# ProtoCAT.net
KiCad netlist of a schematic drawn in EAGLE
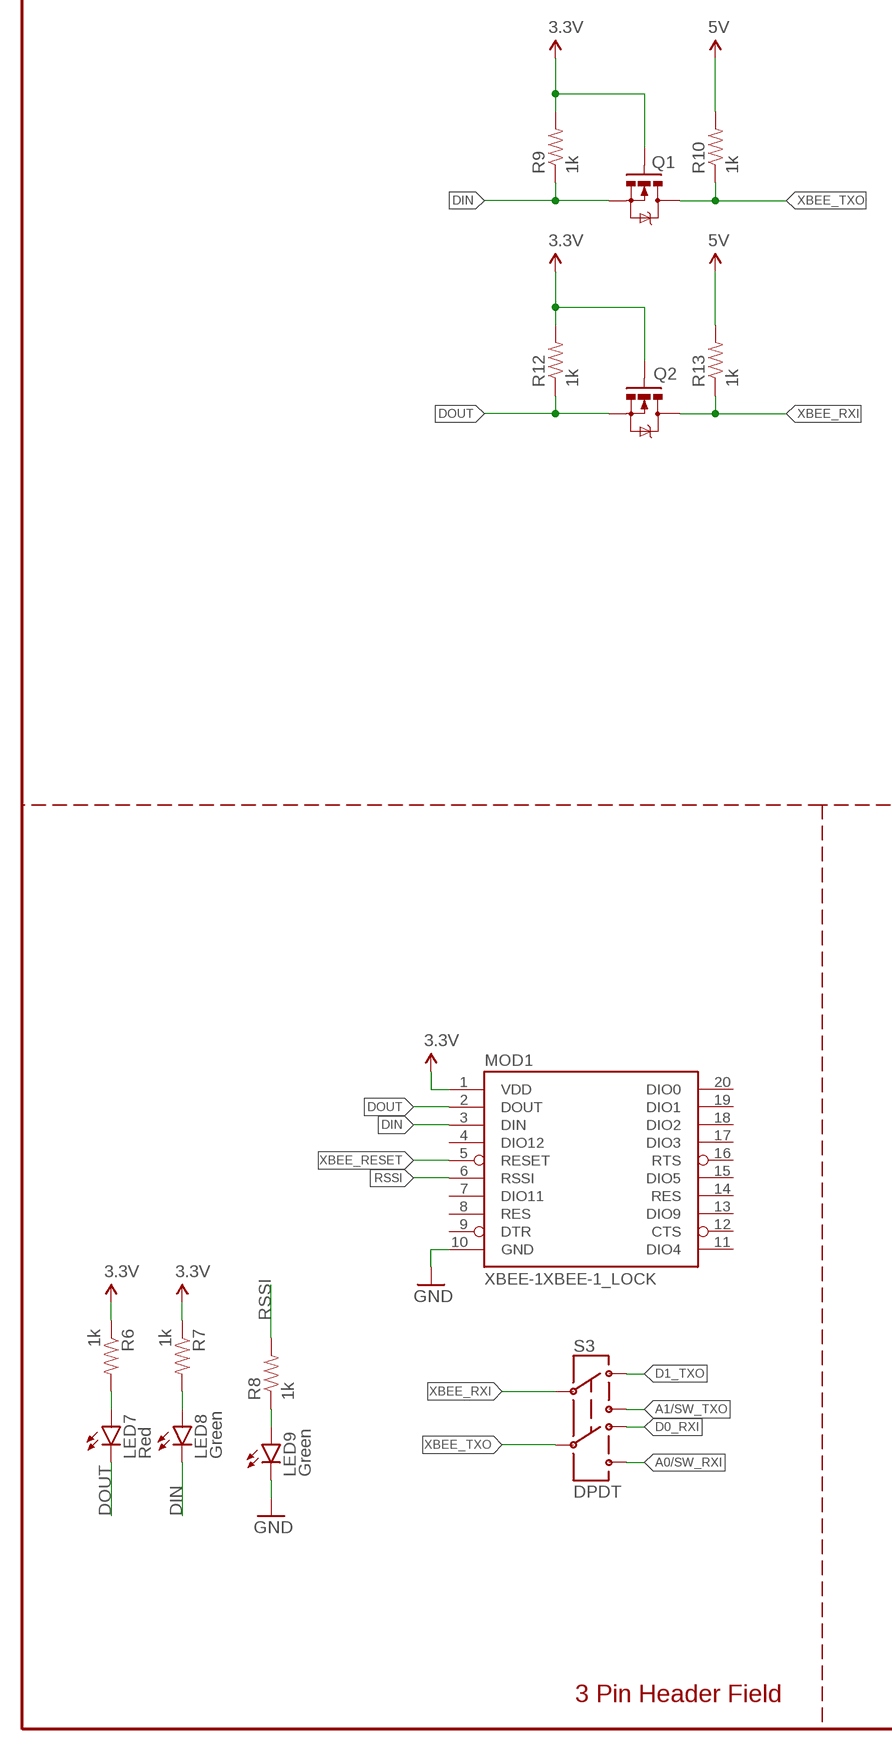
[diagram p0: schematic, sheet 1, part 1 of 2]
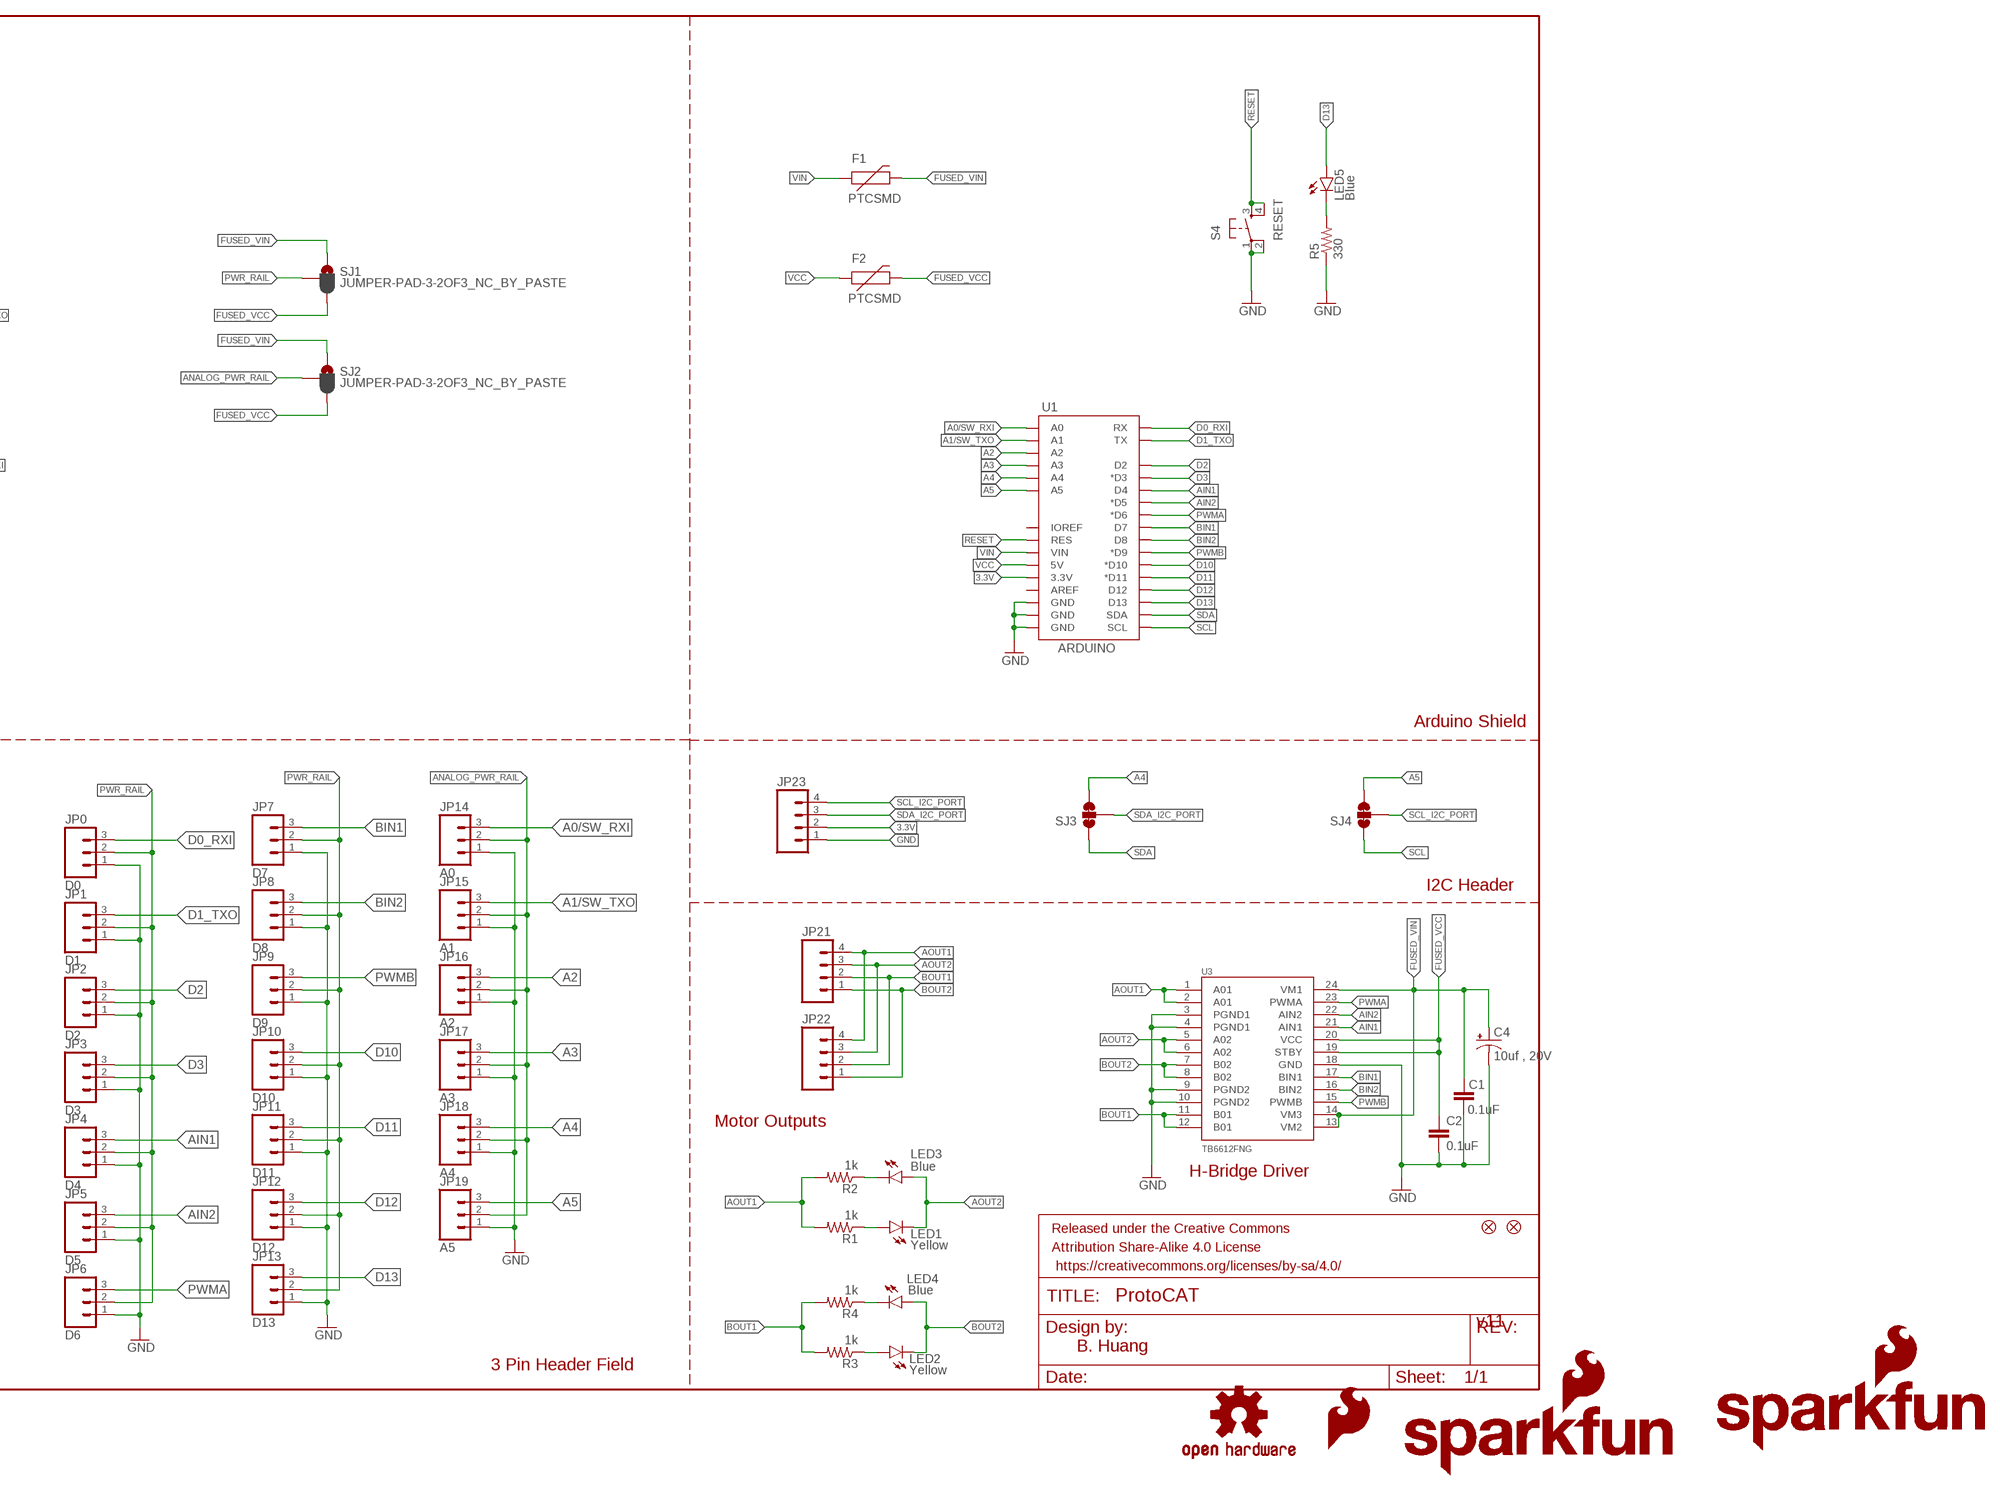
[diagram p1: schematic, sheet 1, part 2 of 2]

(export (version "E")
  (design (tool "Eeschema 10.0.6"))
  (components
    (comp (ref "C1")
      (value "0.1uF")
      (footprint "eagle-import:0603-CAP")
      (libsource (lib "eagle-import") (part "0.1UF-25V-5%(0603)"))
    )
    (comp (ref "C2")
      (value "0.1uF")
      (footprint "eagle-import:0603-CAP")
      (libsource (lib "eagle-import") (part "0.1UF-25V-5%(0603)"))
    )
    (comp (ref "C4")
      (value "10uf , 20V")
      (footprint "eagle-import:EIA3528")
      (libsource (lib "eagle-import") (part "10UF-20V-10%(TANT)"))
    )
    (comp (ref "F1")
      (value "PTCSMD")
      (footprint "eagle-import:PTC-1206")
      (libsource (lib "eagle-import") (part "PTCSMD"))
    )
    (comp (ref "F2")
      (value "PTCSMD")
      (footprint "eagle-import:PTC-1206")
      (libsource (lib "eagle-import") (part "PTCSMD"))
    )
    (comp (ref "FID1")
      (value "FIDUCIAL1X2")
      (footprint "eagle-import:FIDUCIAL-1X2")
      (libsource (lib "eagle-import") (part "FIDUCIAL1X2"))
    )
    (comp (ref "FID2")
      (value "FIDUCIAL1X2")
      (footprint "eagle-import:FIDUCIAL-1X2")
      (libsource (lib "eagle-import") (part "FIDUCIAL1X2"))
    )
    (comp (ref "FRAME1")
      (value "FRAME-LEDGER")
      (footprint "eagle-import:CREATIVE_COMMONS")
      (libsource (lib "eagle-import") (part "FRAME-LEDGER"))
    )
    (comp (ref "JP0")
      (value "D0")
      (footprint "eagle-import:1X03_LOCK")
      (libsource (lib "eagle-import") (part "M03LOCK"))
    )
    (comp (ref "JP1")
      (value "D1")
      (footprint "eagle-import:1X03_LOCK")
      (libsource (lib "eagle-import") (part "M03LOCK"))
    )
    (comp (ref "JP2")
      (value "D2")
      (footprint "eagle-import:1X03_LOCK")
      (libsource (lib "eagle-import") (part "M03LOCK"))
    )
    (comp (ref "JP3")
      (value "D3")
      (footprint "eagle-import:1X03_LOCK")
      (libsource (lib "eagle-import") (part "M03LOCK"))
    )
    (comp (ref "JP4")
      (value "D4")
      (footprint "eagle-import:1X03_LOCK")
      (libsource (lib "eagle-import") (part "M03LOCK"))
    )
    (comp (ref "JP5")
      (value "D5")
      (footprint "eagle-import:1X03_LOCK")
      (libsource (lib "eagle-import") (part "M03LOCK"))
    )
    (comp (ref "JP6")
      (value "D6")
      (footprint "eagle-import:1X03_LOCK")
      (libsource (lib "eagle-import") (part "M03LOCK"))
    )
    (comp (ref "JP7")
      (value "D7")
      (footprint "eagle-import:1X03_LOCK")
      (libsource (lib "eagle-import") (part "M03LOCK"))
    )
    (comp (ref "JP8")
      (value "D8")
      (footprint "eagle-import:1X03_LOCK")
      (libsource (lib "eagle-import") (part "M03LOCK"))
    )
    (comp (ref "JP9")
      (value "D9")
      (footprint "eagle-import:1X03_LOCK")
      (libsource (lib "eagle-import") (part "M03LOCK"))
    )
    (comp (ref "JP10")
      (value "D10")
      (footprint "eagle-import:1X03_LOCK")
      (libsource (lib "eagle-import") (part "M03LOCK"))
    )
    (comp (ref "JP11")
      (value "D11")
      (footprint "eagle-import:1X03_LOCK")
      (libsource (lib "eagle-import") (part "M03LOCK"))
    )
    (comp (ref "JP12")
      (value "D12")
      (footprint "eagle-import:1X03_LOCK")
      (libsource (lib "eagle-import") (part "M03LOCK"))
    )
    (comp (ref "JP13")
      (value "D13")
      (footprint "eagle-import:1X03_LOCK")
      (libsource (lib "eagle-import") (part "M03LOCK"))
    )
    (comp (ref "JP14")
      (value "A0")
      (footprint "eagle-import:1X03_LOCK")
      (libsource (lib "eagle-import") (part "M03LOCK"))
    )
    (comp (ref "JP15")
      (value "A1")
      (footprint "eagle-import:1X03_LOCK")
      (libsource (lib "eagle-import") (part "M03LOCK"))
    )
    (comp (ref "JP16")
      (value "A2")
      (footprint "eagle-import:1X03_LOCK")
      (libsource (lib "eagle-import") (part "M03LOCK"))
    )
    (comp (ref "JP17")
      (value "A3")
      (footprint "eagle-import:1X03_LOCK")
      (libsource (lib "eagle-import") (part "M03LOCK"))
    )
    (comp (ref "JP18")
      (value "A4")
      (footprint "eagle-import:1X03_LOCK")
      (libsource (lib "eagle-import") (part "M03LOCK"))
    )
    (comp (ref "JP19")
      (value "A5")
      (footprint "eagle-import:1X03_LOCK")
      (libsource (lib "eagle-import") (part "M03LOCK"))
    )
    (comp (ref "JP21")
      (value "M04PTH")
      (footprint "eagle-import:1X04")
      (libsource (lib "eagle-import") (part "M04PTH"))
    )
    (comp (ref "JP22")
      (value "M04SMD_STRAIGHT_COMBO")
      (footprint "eagle-import:1X04_SMD_STRAIGHT_COMBO")
      (libsource (lib "eagle-import") (part "M04SMD_STRAIGHT_COMBO"))
    )
    (comp (ref "JP23")
      (value "M04PTH")
      (footprint "eagle-import:1X04")
      (libsource (lib "eagle-import") (part "M04PTH"))
    )
    (comp (ref "LED1")
      (value "Yellow")
      (footprint "eagle-import:LED-0603")
      (libsource (lib "eagle-import") (part "LED0603"))
    )
    (comp (ref "LED2")
      (value "Yellow")
      (footprint "eagle-import:LED-0603")
      (libsource (lib "eagle-import") (part "LED0603"))
    )
    (comp (ref "LED3")
      (value "Blue")
      (footprint "eagle-import:LED-0603")
      (libsource (lib "eagle-import") (part "LED0603"))
    )
    (comp (ref "LED4")
      (value "Blue")
      (footprint "eagle-import:LED-0603")
      (libsource (lib "eagle-import") (part "LED0603"))
    )
    (comp (ref "LED5")
      (value "Blue")
      (footprint "eagle-import:LED-0603")
      (libsource (lib "eagle-import") (part "LED0603"))
    )
    (comp (ref "LED7")
      (value "Red")
      (footprint "eagle-import:LED-0603")
      (libsource (lib "eagle-import") (part "LED-RED0603"))
    )
    (comp (ref "LED8")
      (value "Green")
      (footprint "eagle-import:LED-0603")
      (libsource (lib "eagle-import") (part "LED-GREEN0603"))
    )
    (comp (ref "LED9")
      (value "Green")
      (footprint "eagle-import:LED-0603")
      (libsource (lib "eagle-import") (part "LED-GREEN0603"))
    )
    (comp (ref "LOGO1")
      (value "OSHW-LOGOM")
      (footprint "eagle-import:OSHW-LOGO-M")
      (libsource (lib "eagle-import") (part "OSHW-LOGOM"))
    )
    (comp (ref "LOGO2")
      (value "SFE_LOGO_NAME_FLAME.1_INCH")
      (footprint "eagle-import:SFE_LOGO_NAME_FLAME_.1")
      (libsource (lib "eagle-import") (part "SFE_LOGO_NAME_FLAME.1_INCH"))
    )
    (comp (ref "LOGO3")
      (value "SFE_LOGO_FLAME.2COP")
      (footprint "eagle-import:SFE_LOGO_FLAME_COPPER_.2")
      (libsource (lib "eagle-import") (part "SFE_LOGO_FLAME.2COP"))
    )
    (comp (ref "LOGO4")
      (value "SFE_LOGO_NAME_FLAME.1_INCH")
      (footprint "eagle-import:SFE_LOGO_NAME_FLAME_.1")
      (libsource (lib "eagle-import") (part "SFE_LOGO_NAME_FLAME.1_INCH"))
    )
    (comp (ref "MOD1")
      (value "XBEE-1XBEE-1_LOCK")
      (footprint "eagle-import:XBEE-1_LOCK")
      (libsource (lib "eagle-import") (part "XBEE-1XBEE-1_LOCK"))
    )
    (comp (ref "Q1")
      (value "MOSFET-NCHANNELSMD")
      (footprint "eagle-import:SOT23-3")
      (libsource (lib "eagle-import") (part "MOSFET-NCHANNELSMD"))
    )
    (comp (ref "Q2")
      (value "MOSFET-NCHANNELSMD")
      (footprint "eagle-import:SOT23-3")
      (libsource (lib "eagle-import") (part "MOSFET-NCHANNELSMD"))
    )
    (comp (ref "R1")
      (value "1k")
      (footprint "eagle-import:0603-RES")
      (libsource (lib "eagle-import") (part "1KOHM1/10W1%(0603)"))
    )
    (comp (ref "R2")
      (value "1k")
      (footprint "eagle-import:0603-RES")
      (libsource (lib "eagle-import") (part "1KOHM1/10W1%(0603)"))
    )
    (comp (ref "R3")
      (value "1k")
      (footprint "eagle-import:0603-RES")
      (libsource (lib "eagle-import") (part "1KOHM1/10W1%(0603)"))
    )
    (comp (ref "R4")
      (value "1k")
      (footprint "eagle-import:0603-RES")
      (libsource (lib "eagle-import") (part "1KOHM1/10W1%(0603)"))
    )
    (comp (ref "R5")
      (value "330")
      (footprint "eagle-import:0603-RES")
      (libsource (lib "eagle-import") (part "330OHM1/10W1%(0603)"))
    )
    (comp (ref "R6")
      (value "1k")
      (footprint "eagle-import:0603-RES")
      (libsource (lib "eagle-import") (part "1KOHM1/10W1%(0603)"))
    )
    (comp (ref "R7")
      (value "1k")
      (footprint "eagle-import:0603-RES")
      (libsource (lib "eagle-import") (part "1KOHM1/10W1%(0603)"))
    )
    (comp (ref "R8")
      (value "1k")
      (footprint "eagle-import:0603-RES")
      (libsource (lib "eagle-import") (part "1KOHM1/10W1%(0603)"))
    )
    (comp (ref "R9")
      (value "1k")
      (footprint "eagle-import:0603-RES")
      (libsource (lib "eagle-import") (part "1KOHM1/10W1%(0603)"))
    )
    (comp (ref "R10")
      (value "1k")
      (footprint "eagle-import:0603-RES")
      (libsource (lib "eagle-import") (part "1KOHM1/10W1%(0603)"))
    )
    (comp (ref "R12")
      (value "1k")
      (footprint "eagle-import:0603-RES")
      (libsource (lib "eagle-import") (part "1KOHM1/10W1%(0603)"))
    )
    (comp (ref "R13")
      (value "1k")
      (footprint "eagle-import:0603-RES")
      (libsource (lib "eagle-import") (part "1KOHM1/10W1%(0603)"))
    )
    (comp (ref "S3")
      (value "DPDT")
      (footprint "eagle-import:AYZ0202")
      (fields (field (name "PROD_ID") "SWCH-08179"))
      (libsource (lib "eagle-import") (part "SWITCH-DPDTAYZ0202"))
    )
    (comp (ref "S4")
      (value "RESET")
      (footprint "eagle-import:TACTILE-SWITCH-SMD")
      (libsource (lib "eagle-import") (part "TAC_SWITCHSMD"))
    )
    (comp (ref "SJ1")
      (value "JUMPER-PAD-3-2OF3_NC_BY_PASTE")
      (footprint "eagle-import:PAD-JUMPER-3-2OF3_NC_BY_PASTE_YES_SILK_FULL_BOX")
      (libsource (lib "eagle-import") (part "JUMPER-PAD-3-2OF3_NC_BY_PASTE"))
    )
    (comp (ref "SJ2")
      (value "JUMPER-PAD-3-2OF3_NC_BY_PASTE")
      (footprint "eagle-import:PAD-JUMPER-3-2OF3_NC_BY_PASTE_YES_SILK_FULL_BOX")
      (libsource (lib "eagle-import") (part "JUMPER-PAD-3-2OF3_NC_BY_PASTE"))
    )
    (comp (ref "SJ3")
      (value "JUMPER-PAD-3-NC_BY_TRACE")
      (footprint "eagle-import:PAD-JUMPER-3-3OF3_NC_BY_TRACE_YES_SILK_FULL_BOX")
      (libsource (lib "eagle-import") (part "JUMPER-PAD-3-NC_BY_TRACE"))
    )
    (comp (ref "SJ4")
      (value "JUMPER-PAD-3-NC_BY_TRACE")
      (footprint "eagle-import:PAD-JUMPER-3-3OF3_NC_BY_TRACE_YES_SILK_FULL_BOX")
      (libsource (lib "eagle-import") (part "JUMPER-PAD-3-NC_BY_TRACE"))
    )
    (comp (ref "U$1")
      (value "SFE_LUDUS")
      (footprint "eagle-import:SFE_LUDUS-M")
      (libsource (lib "eagle-import") (part "SFE_LUDUS"))
    )
    (comp (ref "U1")
      (value "ARDUINO")
      (footprint "eagle-import:UNO_R3_SHIELD_NOLABELS")
      (libsource (lib "eagle-import") (part "ARDUINO_R3_SHIELDNOLABELS"))
    )
    (comp (ref "U3")
      (value "TB6612FNG")
      (footprint "eagle-import:SSOP24")
      (libsource (lib "eagle-import") (part "TB6612FNG"))
    )
  )
  (nets
    (net (code "1") (name "3.3V") (class "Default")
      (node (ref "JP23") (pin "2") (pinfunction "2_2") (pintype "passive"))
      (node (ref "MOD1") (pin "1") (pinfunction "VDD_1") (pintype "power_in"))
      (node (ref "Q1") (pin "1") (pinfunction "G_1") (pintype "passive"))
      (node (ref "Q2") (pin "1") (pinfunction "G_1") (pintype "passive"))
      (node (ref "R12") (pin "2") (pinfunction "2_2") (pintype "passive"))
      (node (ref "R6") (pin "1") (pinfunction "1_1") (pintype "passive"))
      (node (ref "R7") (pin "1") (pinfunction "1_1") (pintype "passive"))
      (node (ref "R9") (pin "2") (pinfunction "2_2") (pintype "passive"))
      (node (ref "U1") (pin "3.3V") (pinfunction "3.3V_3.3V") (pintype "bidirectional"))
    )
    (net (code "2") (name "5V") (class "Default")
      (node (ref "R10") (pin "2") (pinfunction "2_2") (pintype "passive"))
      (node (ref "R13") (pin "2") (pinfunction "2_2") (pintype "passive"))
    )
    (net (code "3") (name "A0{slash}SW_RXI") (class "Default")
      (node (ref "JP14") (pin "3") (pinfunction "3_3") (pintype "passive"))
      (node (ref "S3") (pin "6") (pinfunction "6_6") (pintype "bidirectional"))
      (node (ref "U1") (pin "A0") (pinfunction "A0_A0") (pintype "bidirectional"))
    )
    (net (code "4") (name "A1{slash}SW_TXO") (class "Default")
      (node (ref "JP15") (pin "3") (pinfunction "3_3") (pintype "passive"))
      (node (ref "S3") (pin "3") (pinfunction "3_3") (pintype "bidirectional"))
      (node (ref "U1") (pin "A1") (pinfunction "A1_A1") (pintype "bidirectional"))
    )
    (net (code "5") (name "A2") (class "Default")
      (node (ref "JP16") (pin "3") (pinfunction "3_3") (pintype "passive"))
      (node (ref "U1") (pin "A2") (pinfunction "A2_A2") (pintype "bidirectional"))
    )
    (net (code "6") (name "A3") (class "Default")
      (node (ref "JP17") (pin "3") (pinfunction "3_3") (pintype "passive"))
      (node (ref "U1") (pin "A3") (pinfunction "A3_A3") (pintype "bidirectional"))
    )
    (net (code "7") (name "A4") (class "Default")
      (node (ref "JP18") (pin "3") (pinfunction "3_3") (pintype "passive"))
      (node (ref "SJ3") (pin "3") (pinfunction "3_3") (pintype "passive"))
      (node (ref "U1") (pin "A4") (pinfunction "A4_A4") (pintype "bidirectional"))
    )
    (net (code "8") (name "A5") (class "Default")
      (node (ref "JP19") (pin "3") (pinfunction "3_3") (pintype "passive"))
      (node (ref "SJ4") (pin "3") (pinfunction "3_3") (pintype "passive"))
      (node (ref "U1") (pin "A5") (pinfunction "A5_A5") (pintype "bidirectional"))
    )
    (net (code "9") (name "AIN1") (class "Default")
      (node (ref "JP4") (pin "3") (pinfunction "3_3") (pintype "passive"))
      (node (ref "U1") (pin "D4") (pinfunction "D4_D4") (pintype "bidirectional"))
      (node (ref "U3") (pin "21") (pinfunction "AIN1_21") (pintype "bidirectional"))
    )
    (net (code "10") (name "AIN2") (class "Default")
      (node (ref "JP5") (pin "3") (pinfunction "3_3") (pintype "passive"))
      (node (ref "U1") (pin "D5") (pinfunction "*D5_D5") (pintype "bidirectional"))
      (node (ref "U3") (pin "22") (pinfunction "AIN2_22") (pintype "bidirectional"))
    )
    (net (code "11") (name "ANALOG_PWR_RAIL") (class "Default")
      (node (ref "JP14") (pin "2") (pinfunction "2_2") (pintype "passive"))
      (node (ref "JP15") (pin "2") (pinfunction "2_2") (pintype "passive"))
      (node (ref "JP16") (pin "2") (pinfunction "2_2") (pintype "passive"))
      (node (ref "JP17") (pin "2") (pinfunction "2_2") (pintype "passive"))
      (node (ref "JP18") (pin "2") (pinfunction "2_2") (pintype "passive"))
      (node (ref "JP19") (pin "2") (pinfunction "2_2") (pintype "passive"))
      (node (ref "SJ2") (pin "2") (pinfunction "2_2") (pintype "passive"))
    )
    (net (code "12") (name "AOUT1") (class "Default")
      (node (ref "JP21") (pin "4") (pinfunction "4_4") (pintype "passive"))
      (node (ref "JP22") (pin "4") (pinfunction "4_4") (pintype "passive"))
      (node (ref "R1") (pin "2") (pinfunction "2_2") (pintype "passive"))
      (node (ref "R2") (pin "2") (pinfunction "2_2") (pintype "passive"))
      (node (ref "U3") (pin "1") (pinfunction "A01_1") (pintype "bidirectional"))
      (node (ref "U3") (pin "2") (pinfunction "A01_2") (pintype "bidirectional"))
    )
    (net (code "13") (name "AOUT2") (class "Default")
      (node (ref "JP21") (pin "3") (pinfunction "3_3") (pintype "passive"))
      (node (ref "JP22") (pin "3") (pinfunction "3_3") (pintype "passive"))
      (node (ref "LED1") (pin "C") (pinfunction "C_C") (pintype "passive"))
      (node (ref "LED3") (pin "A") (pinfunction "A_A") (pintype "passive"))
      (node (ref "U3") (pin "5") (pinfunction "A02_5") (pintype "bidirectional"))
      (node (ref "U3") (pin "6") (pinfunction "A02_6") (pintype "bidirectional"))
    )
    (net (code "14") (name "BIN1") (class "Default")
      (node (ref "JP7") (pin "3") (pinfunction "3_3") (pintype "passive"))
      (node (ref "U1") (pin "D7") (pinfunction "D7_D7") (pintype "bidirectional"))
      (node (ref "U3") (pin "17") (pinfunction "BIN1_17") (pintype "bidirectional"))
    )
    (net (code "15") (name "BIN2") (class "Default")
      (node (ref "JP8") (pin "3") (pinfunction "3_3") (pintype "passive"))
      (node (ref "U1") (pin "D8") (pinfunction "D8_D8") (pintype "bidirectional"))
      (node (ref "U3") (pin "16") (pinfunction "BIN2_16") (pintype "bidirectional"))
    )
    (net (code "16") (name "BOUT1") (class "Default")
      (node (ref "JP21") (pin "2") (pinfunction "2_2") (pintype "passive"))
      (node (ref "JP22") (pin "2") (pinfunction "2_2") (pintype "passive"))
      (node (ref "R3") (pin "2") (pinfunction "2_2") (pintype "passive"))
      (node (ref "R4") (pin "2") (pinfunction "2_2") (pintype "passive"))
      (node (ref "U3") (pin "11") (pinfunction "B01_11") (pintype "bidirectional"))
      (node (ref "U3") (pin "12") (pinfunction "B01_12") (pintype "bidirectional"))
    )
    (net (code "17") (name "BOUT2") (class "Default")
      (node (ref "JP21") (pin "1") (pinfunction "1_1") (pintype "passive"))
      (node (ref "JP22") (pin "1") (pinfunction "1_1") (pintype "passive"))
      (node (ref "LED2") (pin "C") (pinfunction "C_C") (pintype "passive"))
      (node (ref "LED4") (pin "A") (pinfunction "A_A") (pintype "passive"))
      (node (ref "U3") (pin "7") (pinfunction "B02_7") (pintype "bidirectional"))
      (node (ref "U3") (pin "8") (pinfunction "B02_8") (pintype "bidirectional"))
    )
    (net (code "18") (name "D0_RXI") (class "Default")
      (node (ref "JP0") (pin "3") (pinfunction "3_3") (pintype "passive"))
      (node (ref "S3") (pin "4") (pinfunction "4_4") (pintype "bidirectional"))
      (node (ref "U1") (pin "RX") (pinfunction "RX_RX") (pintype "bidirectional"))
    )
    (net (code "19") (name "D1_TXO") (class "Default")
      (node (ref "JP1") (pin "3") (pinfunction "3_3") (pintype "passive"))
      (node (ref "S3") (pin "1") (pinfunction "1_1") (pintype "bidirectional"))
      (node (ref "U1") (pin "TX") (pinfunction "TX_TX") (pintype "bidirectional"))
    )
    (net (code "20") (name "D2") (class "Default")
      (node (ref "JP2") (pin "3") (pinfunction "3_3") (pintype "passive"))
      (node (ref "U1") (pin "D2") (pinfunction "D2_D2") (pintype "bidirectional"))
    )
    (net (code "21") (name "D3") (class "Default")
      (node (ref "JP3") (pin "3") (pinfunction "3_3") (pintype "passive"))
      (node (ref "U1") (pin "D3") (pinfunction "*D3_D3") (pintype "bidirectional"))
    )
    (net (code "22") (name "D10") (class "Default")
      (node (ref "JP10") (pin "3") (pinfunction "3_3") (pintype "passive"))
      (node (ref "U1") (pin "D10") (pinfunction "*D10_D10") (pintype "bidirectional"))
    )
    (net (code "23") (name "D11") (class "Default")
      (node (ref "JP11") (pin "3") (pinfunction "3_3") (pintype "passive"))
      (node (ref "U1") (pin "D11") (pinfunction "*D11_D11") (pintype "bidirectional"))
    )
    (net (code "24") (name "D12") (class "Default")
      (node (ref "JP12") (pin "3") (pinfunction "3_3") (pintype "passive"))
      (node (ref "U1") (pin "D12") (pinfunction "D12_D12") (pintype "bidirectional"))
    )
    (net (code "25") (name "D13") (class "Default")
      (node (ref "JP13") (pin "3") (pinfunction "3_3") (pintype "passive"))
      (node (ref "LED5") (pin "A") (pinfunction "A_A") (pintype "passive"))
      (node (ref "U1") (pin "D13") (pinfunction "D13_D13") (pintype "bidirectional"))
    )
    (net (code "26") (name "DIN") (class "Default")
      (node (ref "LED8") (pin "C") (pinfunction "C_C") (pintype "passive"))
      (node (ref "MOD1") (pin "3") (pinfunction "DIN_3") (pintype "input"))
      (node (ref "Q1") (pin "2") (pinfunction "S_2") (pintype "passive"))
      (node (ref "R9") (pin "1") (pinfunction "1_1") (pintype "passive"))
    )
    (net (code "27") (name "DOUT") (class "Default")
      (node (ref "LED7") (pin "C") (pinfunction "C_C") (pintype "passive"))
      (node (ref "MOD1") (pin "2") (pinfunction "DOUT_2") (pintype "output"))
      (node (ref "Q2") (pin "2") (pinfunction "S_2") (pintype "passive"))
      (node (ref "R12") (pin "1") (pinfunction "1_1") (pintype "passive"))
    )
    (net (code "28") (name "FUSED_VCC") (class "Default")
      (node (ref "C2") (pin "1") (pinfunction "1_1") (pintype "passive"))
      (node (ref "F2") (pin "2") (pinfunction "2_2") (pintype "bidirectional"))
      (node (ref "SJ1") (pin "3") (pinfunction "3_3") (pintype "passive"))
      (node (ref "SJ2") (pin "3") (pinfunction "3_3") (pintype "passive"))
      (node (ref "U3") (pin "19") (pinfunction "STBY_19") (pintype "bidirectional"))
      (node (ref "U3") (pin "20") (pinfunction "VCC_20") (pintype "bidirectional"))
    )
    (net (code "29") (name "FUSED_VIN") (class "Default")
      (node (ref "C1") (pin "1") (pinfunction "1_1") (pintype "passive"))
      (node (ref "C4") (pin "A") (pinfunction "+_A") (pintype "passive"))
      (node (ref "F1") (pin "2") (pinfunction "2_2") (pintype "bidirectional"))
      (node (ref "SJ1") (pin "1") (pinfunction "1_1") (pintype "passive"))
      (node (ref "SJ2") (pin "1") (pinfunction "1_1") (pintype "passive"))
      (node (ref "U3") (pin "13") (pinfunction "VM2_13") (pintype "bidirectional"))
      (node (ref "U3") (pin "14") (pinfunction "VM3_14") (pintype "bidirectional"))
      (node (ref "U3") (pin "24") (pinfunction "VM1_24") (pintype "bidirectional"))
    )
    (net (code "30") (name "GND") (class "Default")
      (node (ref "C1") (pin "2") (pinfunction "2_2") (pintype "passive"))
      (node (ref "C2") (pin "2") (pinfunction "2_2") (pintype "passive"))
      (node (ref "C4") (pin "C") (pinfunction "-_C") (pintype "passive"))
      (node (ref "JP0") (pin "1") (pinfunction "1_1") (pintype "passive"))
      (node (ref "JP1") (pin "1") (pinfunction "1_1") (pintype "passive"))
      (node (ref "JP10") (pin "1") (pinfunction "1_1") (pintype "passive"))
      (node (ref "JP11") (pin "1") (pinfunction "1_1") (pintype "passive"))
      (node (ref "JP12") (pin "1") (pinfunction "1_1") (pintype "passive"))
      (node (ref "JP13") (pin "1") (pinfunction "1_1") (pintype "passive"))
      (node (ref "JP14") (pin "1") (pinfunction "1_1") (pintype "passive"))
      (node (ref "JP15") (pin "1") (pinfunction "1_1") (pintype "passive"))
      (node (ref "JP16") (pin "1") (pinfunction "1_1") (pintype "passive"))
      (node (ref "JP17") (pin "1") (pinfunction "1_1") (pintype "passive"))
      (node (ref "JP18") (pin "1") (pinfunction "1_1") (pintype "passive"))
      (node (ref "JP19") (pin "1") (pinfunction "1_1") (pintype "passive"))
      (node (ref "JP2") (pin "1") (pinfunction "1_1") (pintype "passive"))
      (node (ref "JP23") (pin "1") (pinfunction "1_1") (pintype "passive"))
      (node (ref "JP3") (pin "1") (pinfunction "1_1") (pintype "passive"))
      (node (ref "JP4") (pin "1") (pinfunction "1_1") (pintype "passive"))
      (node (ref "JP5") (pin "1") (pinfunction "1_1") (pintype "passive"))
      (node (ref "JP6") (pin "1") (pinfunction "1_1") (pintype "passive"))
      (node (ref "JP7") (pin "1") (pinfunction "1_1") (pintype "passive"))
      (node (ref "JP8") (pin "1") (pinfunction "1_1") (pintype "passive"))
      (node (ref "JP9") (pin "1") (pinfunction "1_1") (pintype "passive"))
      (node (ref "LED9") (pin "C") (pinfunction "C_C") (pintype "passive"))
      (node (ref "MOD1") (pin "10") (pinfunction "GND_10") (pintype "power_in"))
      (node (ref "R5") (pin "1") (pinfunction "1_1") (pintype "passive"))
      (node (ref "S4") (pin "1") (pinfunction "1_1") (pintype "passive"))
      (node (ref "S4") (pin "2") (pinfunction "2_2") (pintype "passive"))
      (node (ref "U1") (pin "GND@0") (pinfunction "GND_GND@0") (pintype "bidirectional"))
      (node (ref "U1") (pin "GND@1") (pinfunction "GND_GND@1") (pintype "bidirectional"))
      (node (ref "U1") (pin "GND@2") (pinfunction "GND_GND@2") (pintype "bidirectional"))
      (node (ref "U3") (pin "10") (pinfunction "PGND2_10") (pintype "bidirectional"))
      (node (ref "U3") (pin "18") (pinfunction "GND_18") (pintype "bidirectional"))
      (node (ref "U3") (pin "3") (pinfunction "PGND1_3") (pintype "bidirectional"))
      (node (ref "U3") (pin "4") (pinfunction "PGND1_4") (pintype "bidirectional"))
      (node (ref "U3") (pin "9") (pinfunction "PGND2_9") (pintype "bidirectional"))
    )
    (net (code "31") (name "Net-(LED1-PadA)") (class "Default")
      (node (ref "LED1") (pin "A") (pinfunction "A_A") (pintype "passive"))
      (node (ref "R1") (pin "1") (pinfunction "1_1") (pintype "passive"))
    )
    (net (code "32") (name "Net-(LED2-PadA)") (class "Default")
      (node (ref "LED2") (pin "A") (pinfunction "A_A") (pintype "passive"))
      (node (ref "R3") (pin "1") (pinfunction "1_1") (pintype "passive"))
    )
    (net (code "33") (name "Net-(LED3-PadC)") (class "Default")
      (node (ref "LED3") (pin "C") (pinfunction "C_C") (pintype "passive"))
      (node (ref "R2") (pin "1") (pinfunction "1_1") (pintype "passive"))
    )
    (net (code "34") (name "Net-(LED4-PadC)") (class "Default")
      (node (ref "LED4") (pin "C") (pinfunction "C_C") (pintype "passive"))
      (node (ref "R4") (pin "1") (pinfunction "1_1") (pintype "passive"))
    )
    (net (code "35") (name "Net-(LED5-PadC)") (class "Default")
      (node (ref "LED5") (pin "C") (pinfunction "C_C") (pintype "passive"))
      (node (ref "R5") (pin "2") (pinfunction "2_2") (pintype "passive"))
    )
    (net (code "36") (name "Net-(LED7-PadA)") (class "Default")
      (node (ref "LED7") (pin "A") (pinfunction "A_A") (pintype "passive"))
      (node (ref "R6") (pin "2") (pinfunction "2_2") (pintype "passive"))
    )
    (net (code "37") (name "Net-(LED8-PadA)") (class "Default")
      (node (ref "LED8") (pin "A") (pinfunction "A_A") (pintype "passive"))
      (node (ref "R7") (pin "2") (pinfunction "2_2") (pintype "passive"))
    )
    (net (code "38") (name "Net-(LED9-PadA)") (class "Default")
      (node (ref "LED9") (pin "A") (pinfunction "A_A") (pintype "passive"))
      (node (ref "R8") (pin "1") (pinfunction "1_1") (pintype "passive"))
    )
    (net (code "39") (name "PWMA") (class "Default")
      (node (ref "JP6") (pin "3") (pinfunction "3_3") (pintype "passive"))
      (node (ref "U1") (pin "D6") (pinfunction "*D6_D6") (pintype "bidirectional"))
      (node (ref "U3") (pin "23") (pinfunction "PWMA_23") (pintype "bidirectional"))
    )
    (net (code "40") (name "PWMB") (class "Default")
      (node (ref "JP9") (pin "3") (pinfunction "3_3") (pintype "passive"))
      (node (ref "U1") (pin "D9") (pinfunction "*D9_D9") (pintype "bidirectional"))
      (node (ref "U3") (pin "15") (pinfunction "PWMB_15") (pintype "bidirectional"))
    )
    (net (code "41") (name "PWR_RAIL") (class "Default")
      (node (ref "JP0") (pin "2") (pinfunction "2_2") (pintype "passive"))
      (node (ref "JP1") (pin "2") (pinfunction "2_2") (pintype "passive"))
      (node (ref "JP10") (pin "2") (pinfunction "2_2") (pintype "passive"))
      (node (ref "JP11") (pin "2") (pinfunction "2_2") (pintype "passive"))
      (node (ref "JP12") (pin "2") (pinfunction "2_2") (pintype "passive"))
      (node (ref "JP13") (pin "2") (pinfunction "2_2") (pintype "passive"))
      (node (ref "JP2") (pin "2") (pinfunction "2_2") (pintype "passive"))
      (node (ref "JP3") (pin "2") (pinfunction "2_2") (pintype "passive"))
      (node (ref "JP4") (pin "2") (pinfunction "2_2") (pintype "passive"))
      (node (ref "JP5") (pin "2") (pinfunction "2_2") (pintype "passive"))
      (node (ref "JP6") (pin "2") (pinfunction "2_2") (pintype "passive"))
      (node (ref "JP7") (pin "2") (pinfunction "2_2") (pintype "passive"))
      (node (ref "JP8") (pin "2") (pinfunction "2_2") (pintype "passive"))
      (node (ref "JP9") (pin "2") (pinfunction "2_2") (pintype "passive"))
      (node (ref "SJ1") (pin "2") (pinfunction "2_2") (pintype "passive"))
    )
    (net (code "42") (name "RESET") (class "Default")
      (node (ref "S4") (pin "3") (pinfunction "3_3") (pintype "passive"))
      (node (ref "S4") (pin "4") (pinfunction "4_4") (pintype "passive"))
      (node (ref "U1") (pin "RES") (pinfunction "RES_RES") (pintype "bidirectional"))
    )
    (net (code "43") (name "RSSI") (class "Default")
      (node (ref "MOD1") (pin "6") (pinfunction "RSSI_6") (pintype "bidirectional"))
      (node (ref "R8") (pin "2") (pinfunction "2_2") (pintype "passive"))
    )
    (net (code "44") (name "SCL") (class "Default")
      (node (ref "SJ4") (pin "1") (pinfunction "1_1") (pintype "passive"))
      (node (ref "U1") (pin "SCL") (pinfunction "SCL_SCL") (pintype "bidirectional"))
    )
    (net (code "45") (name "SCL_I2C_PORT") (class "Default")
      (node (ref "JP23") (pin "4") (pinfunction "4_4") (pintype "passive"))
      (node (ref "SJ4") (pin "2") (pinfunction "2_2") (pintype "passive"))
    )
    (net (code "46") (name "SDA") (class "Default")
      (node (ref "SJ3") (pin "1") (pinfunction "1_1") (pintype "passive"))
      (node (ref "U1") (pin "SDA") (pinfunction "SDA_SDA") (pintype "bidirectional"))
    )
    (net (code "47") (name "SDA_I2C_PORT") (class "Default")
      (node (ref "JP23") (pin "3") (pinfunction "3_3") (pintype "passive"))
      (node (ref "SJ3") (pin "2") (pinfunction "2_2") (pintype "passive"))
    )
    (net (code "48") (name "VCC") (class "Default")
      (node (ref "F2") (pin "1") (pinfunction "1_1") (pintype "bidirectional"))
      (node (ref "U1") (pin "5V") (pinfunction "5V_5V") (pintype "bidirectional"))
    )
    (net (code "49") (name "VIN") (class "Default")
      (node (ref "F1") (pin "1") (pinfunction "1_1") (pintype "bidirectional"))
      (node (ref "U1") (pin "VIN") (pinfunction "VIN_VIN") (pintype "bidirectional"))
    )
    (net (code "50") (name "XBEE_RESET") (class "Default")
      (node (ref "MOD1") (pin "5") (pinfunction "RESET_5") (pintype "input"))
    )
    (net (code "51") (name "XBEE_RXI") (class "Default")
      (node (ref "Q2") (pin "3") (pinfunction "D_3") (pintype "passive"))
      (node (ref "R13") (pin "1") (pinfunction "1_1") (pintype "passive"))
      (node (ref "S3") (pin "2") (pinfunction "2_2") (pintype "bidirectional"))
    )
    (net (code "52") (name "XBEE_TXO") (class "Default")
      (node (ref "Q1") (pin "3") (pinfunction "D_3") (pintype "passive"))
      (node (ref "R10") (pin "1") (pinfunction "1_1") (pintype "passive"))
      (node (ref "S3") (pin "5") (pinfunction "5_5") (pintype "bidirectional"))
    )
    (net (code "53") (name "unconnected-(MOD1-CTS-Pad12)") (class "Default")
      (node (ref "MOD1") (pin "12") (pinfunction "CTS_12") (pintype "output"))
    )
    (net (code "54") (name "unconnected-(MOD1-DIO0-Pad20)") (class "Default")
      (node (ref "MOD1") (pin "20") (pinfunction "DIO0_20") (pintype "bidirectional"))
    )
    (net (code "55") (name "unconnected-(MOD1-DIO1-Pad19)") (class "Default")
      (node (ref "MOD1") (pin "19") (pinfunction "DIO1_19") (pintype "bidirectional"))
    )
    (net (code "56") (name "unconnected-(MOD1-DIO2-Pad18)") (class "Default")
      (node (ref "MOD1") (pin "18") (pinfunction "DIO2_18") (pintype "bidirectional"))
    )
    (net (code "57") (name "unconnected-(MOD1-DIO3-Pad17)") (class "Default")
      (node (ref "MOD1") (pin "17") (pinfunction "DIO3_17") (pintype "bidirectional"))
    )
    (net (code "58") (name "unconnected-(MOD1-DIO4-Pad11)") (class "Default")
      (node (ref "MOD1") (pin "11") (pinfunction "DIO4_11") (pintype "bidirectional"))
    )
    (net (code "59") (name "unconnected-(MOD1-DIO5-Pad15)") (class "Default")
      (node (ref "MOD1") (pin "15") (pinfunction "DIO5_15") (pintype "bidirectional"))
    )
    (net (code "60") (name "unconnected-(MOD1-DIO9-Pad13)") (class "Default")
      (node (ref "MOD1") (pin "13") (pinfunction "DIO9_13") (pintype "bidirectional"))
    )
    (net (code "61") (name "unconnected-(MOD1-DIO11-Pad7)") (class "Default")
      (node (ref "MOD1") (pin "7") (pinfunction "DIO11_7") (pintype "bidirectional"))
    )
    (net (code "62") (name "unconnected-(MOD1-DIO12-Pad4)") (class "Default")
      (node (ref "MOD1") (pin "4") (pinfunction "DIO12_4") (pintype "bidirectional"))
    )
    (net (code "63") (name "unconnected-(MOD1-DTR-Pad9)") (class "Default")
      (node (ref "MOD1") (pin "9") (pinfunction "DTR_9") (pintype "bidirectional"))
    )
    (net (code "64") (name "unconnected-(MOD1-RES-Pad8)") (class "Default")
      (node (ref "MOD1") (pin "8") (pinfunction "RES_8") (pintype "bidirectional"))
    )
    (net (code "65") (name "unconnected-(MOD1-RES-Pad14)") (class "Default")
      (node (ref "MOD1") (pin "14") (pinfunction "RES_14") (pintype "bidirectional"))
    )
    (net (code "66") (name "unconnected-(MOD1-RTS-Pad16)") (class "Default")
      (node (ref "MOD1") (pin "16") (pinfunction "RTS_16") (pintype "input"))
    )
    (net (code "67") (name "unconnected-(U1-PadAREF)") (class "Default")
      (node (ref "U1") (pin "AREF") (pinfunction "AREF_AREF") (pintype "bidirectional"))
    )
    (net (code "68") (name "unconnected-(U1-PadIOREF)") (class "Default")
      (node (ref "U1") (pin "IOREF") (pinfunction "IOREF_IOREF") (pintype "bidirectional"))
    )
  )
)
